# commucation.net
KiCad netlist of a schematic drawn in Altium Designer
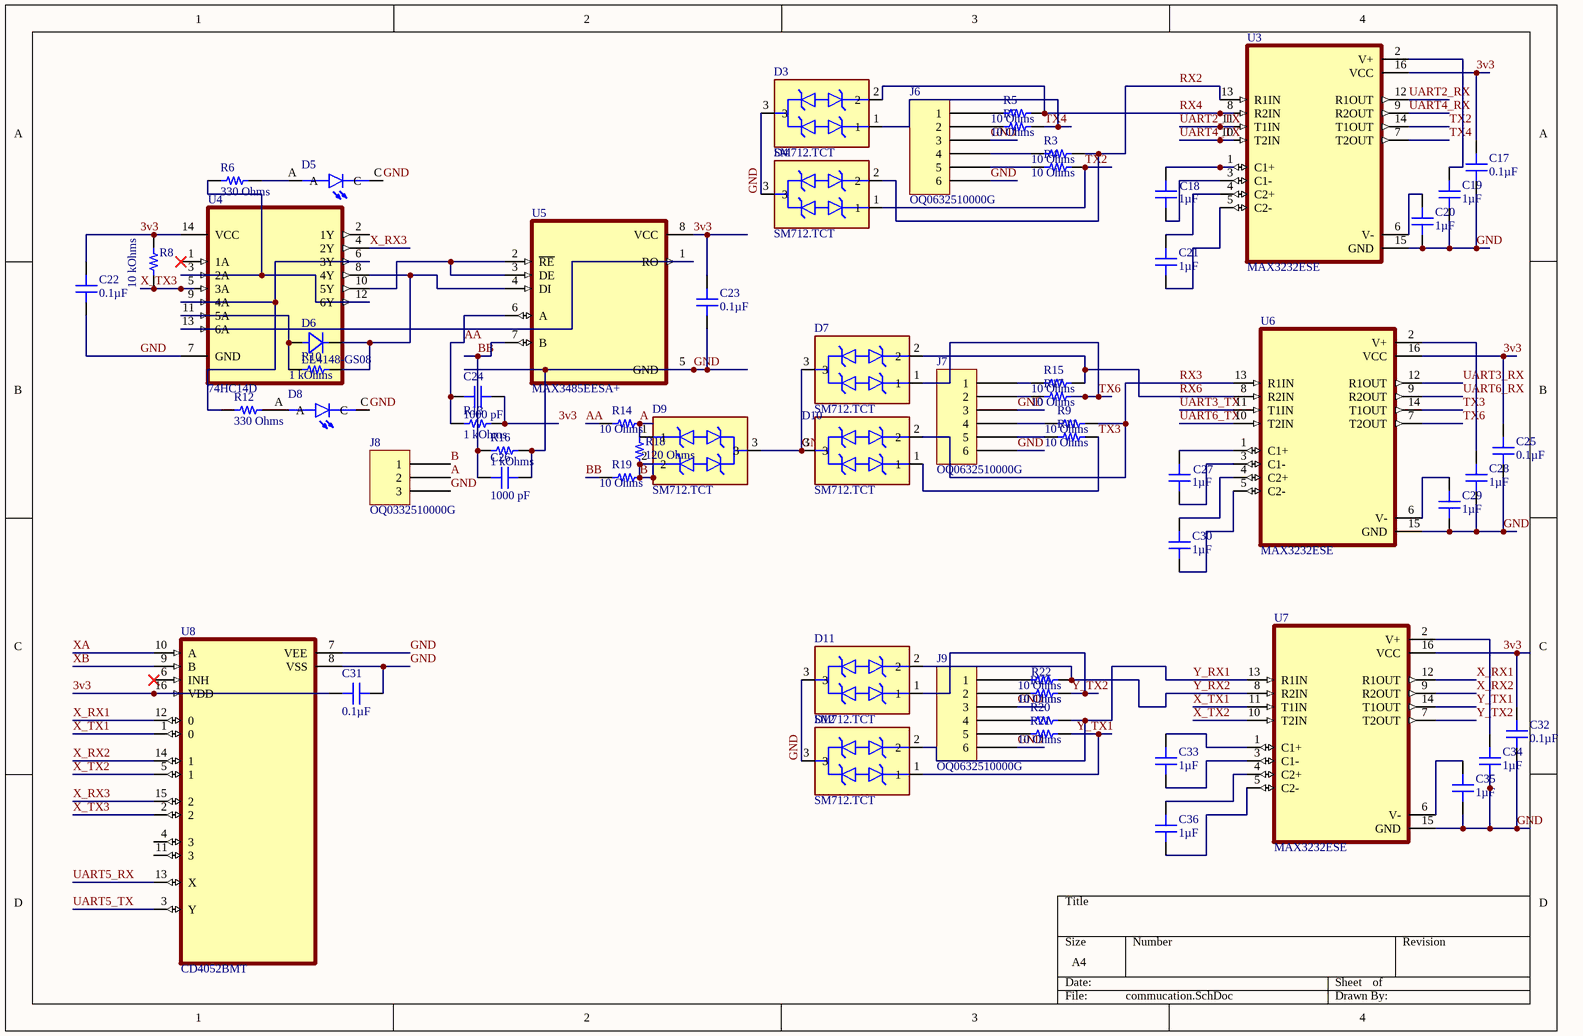
[diagram p0: commucation.SchDoc]

(export (version "E")
  (design (tool "Eeschema 10.0.6"))
  (components
    (comp (ref "C17")
      (value "1µF")
      (footprint "CAP 0805_2012")
      (description "CAP CER 1UF 10V X7R 0805")
      (fields
        (field (name "PART NUMBER") "0805ZC105KAT4A")
        (field (name "CAPACITANCE") "0.1µF")
        (field (name "MANUFACTURER") "AVX Corporation")
      )
      (libsource (lib "Celestial Altium Library - altium_library") (part "Capacitor"))
    )
    (comp (ref "C18")
      (value "1µF")
      (footprint "CAP 0805_2012")
      (description "CAP CER 1UF 10V X7R 0805")
      (fields
        (field (name "PART NUMBER") "0805ZC105KAT4A")
        (field (name "CAPACITANCE") "1µF")
        (field (name "MANUFACTURER") "AVX Corporation")
      )
      (libsource (lib "Celestial Altium Library - altium_library") (part "Capacitor"))
    )
    (comp (ref "C19")
      (value "1µF")
      (footprint "CAP 0805_2012")
      (description "CAP CER 1UF 10V X7R 0805")
      (fields
        (field (name "PART NUMBER") "0805ZC105KAT4A")
        (field (name "CAPACITANCE") "1µF")
        (field (name "MANUFACTURER") "AVX Corporation")
      )
      (libsource (lib "Celestial Altium Library - altium_library") (part "Capacitor"))
    )
    (comp (ref "C20")
      (value "1µF")
      (footprint "CAP 0805_2012")
      (description "CAP CER 1UF 10V X7R 0805")
      (fields
        (field (name "PART NUMBER") "0805ZC105KAT4A")
        (field (name "CAPACITANCE") "1µF")
        (field (name "MANUFACTURER") "AVX Corporation")
      )
      (libsource (lib "Celestial Altium Library - altium_library") (part "Capacitor"))
    )
    (comp (ref "C21")
      (value "1µF")
      (footprint "CAP 0805_2012")
      (description "CAP CER 1UF 10V X7R 0805")
      (fields
        (field (name "PART NUMBER") "0805ZC105KAT4A")
        (field (name "CAPACITANCE") "1µF")
        (field (name "MANUFACTURER") "AVX Corporation")
      )
      (libsource (lib "Celestial Altium Library - altium_library") (part "Capacitor"))
    )
    (comp (ref "C22")
      (value "1µF")
      (footprint "CAP 0805_2012")
      (description "CAP CER 1UF 10V X7R 0805")
      (fields
        (field (name "PART NUMBER") "0805ZC105KAT4A")
        (field (name "CAPACITANCE") "0.1µF")
        (field (name "MANUFACTURER") "AVX Corporation")
      )
      (libsource (lib "Celestial Altium Library - altium_library") (part "Capacitor"))
    )
    (comp (ref "C23")
      (value "1µF")
      (footprint "CAP 0805_2012")
      (description "CAP CER 1UF 10V X7R 0805")
      (fields
        (field (name "PART NUMBER") "0805ZC105KAT4A")
        (field (name "CAPACITANCE") "0.1µF")
        (field (name "MANUFACTURER") "AVX Corporation")
      )
      (libsource (lib "Celestial Altium Library - altium_library") (part "Capacitor"))
    )
    (comp (ref "C24")
      (value "1000 pF")
      (footprint "CAP 0805_2012")
      (description "CAP CER 0805 1NF 25V ULTRA STABL")
      (fields
        (field (name "PART NUMBER") "C0805C102F3HACAUTO")
        (field (name "CAPACITANCE") "1000 pF")
        (field (name "MANUFACTURER") "KEMET")
      )
      (libsource (lib "Celestial Altium Library - altium_library") (part "Capacitor"))
    )
    (comp (ref "C25")
      (value "1µF")
      (footprint "CAP 0805_2012")
      (description "CAP CER 1UF 10V X7R 0805")
      (fields
        (field (name "PART NUMBER") "0805ZC105KAT4A")
        (field (name "CAPACITANCE") "0.1µF")
        (field (name "MANUFACTURER") "AVX Corporation")
      )
      (libsource (lib "Celestial Altium Library - altium_library") (part "Capacitor"))
    )
    (comp (ref "C26")
      (value "1000 pF")
      (footprint "CAP 0805_2012")
      (description "CAP CER 0805 1NF 25V ULTRA STABL")
      (fields
        (field (name "PART NUMBER") "C0805C102F3HACAUTO")
        (field (name "CAPACITANCE") "1000 pF")
        (field (name "MANUFACTURER") "KEMET")
      )
      (libsource (lib "Celestial Altium Library - altium_library") (part "Capacitor"))
    )
    (comp (ref "C27")
      (value "1µF")
      (footprint "CAP 0805_2012")
      (description "CAP CER 1UF 10V X7R 0805")
      (fields
        (field (name "PART NUMBER") "0805ZC105KAT4A")
        (field (name "CAPACITANCE") "1µF")
        (field (name "MANUFACTURER") "AVX Corporation")
      )
      (libsource (lib "Celestial Altium Library - altium_library") (part "Capacitor"))
    )
    (comp (ref "C28")
      (value "1µF")
      (footprint "CAP 0805_2012")
      (description "CAP CER 1UF 10V X7R 0805")
      (fields
        (field (name "PART NUMBER") "0805ZC105KAT4A")
        (field (name "CAPACITANCE") "1µF")
        (field (name "MANUFACTURER") "AVX Corporation")
      )
      (libsource (lib "Celestial Altium Library - altium_library") (part "Capacitor"))
    )
    (comp (ref "C29")
      (value "1µF")
      (footprint "CAP 0805_2012")
      (description "CAP CER 1UF 10V X7R 0805")
      (fields
        (field (name "PART NUMBER") "0805ZC105KAT4A")
        (field (name "CAPACITANCE") "1µF")
        (field (name "MANUFACTURER") "AVX Corporation")
      )
      (libsource (lib "Celestial Altium Library - altium_library") (part "Capacitor"))
    )
    (comp (ref "C30")
      (value "1µF")
      (footprint "CAP 0805_2012")
      (description "CAP CER 1UF 10V X7R 0805")
      (fields
        (field (name "PART NUMBER") "0805ZC105KAT4A")
        (field (name "CAPACITANCE") "1µF")
        (field (name "MANUFACTURER") "AVX Corporation")
      )
      (libsource (lib "Celestial Altium Library - altium_library") (part "Capacitor"))
    )
    (comp (ref "C31")
      (value "1µF")
      (footprint "CAP 0805_2012")
      (description "CAP CER 1UF 10V X7R 0805")
      (fields
        (field (name "PART NUMBER") "0805ZC105KAT4A")
        (field (name "CAPACITANCE") "0.1µF")
        (field (name "MANUFACTURER") "AVX Corporation")
      )
      (libsource (lib "Celestial Altium Library - altium_library") (part "Capacitor"))
    )
    (comp (ref "C32")
      (value "1µF")
      (footprint "CAP 0805_2012")
      (description "CAP CER 1UF 10V X7R 0805")
      (fields
        (field (name "PART NUMBER") "0805ZC105KAT4A")
        (field (name "CAPACITANCE") "0.1µF")
        (field (name "MANUFACTURER") "AVX Corporation")
      )
      (libsource (lib "Celestial Altium Library - altium_library") (part "Capacitor"))
    )
    (comp (ref "C33")
      (value "1µF")
      (footprint "CAP 0805_2012")
      (description "CAP CER 1UF 10V X7R 0805")
      (fields
        (field (name "PART NUMBER") "0805ZC105KAT4A")
        (field (name "CAPACITANCE") "1µF")
        (field (name "MANUFACTURER") "AVX Corporation")
      )
      (libsource (lib "Celestial Altium Library - altium_library") (part "Capacitor"))
    )
    (comp (ref "C34")
      (value "1µF")
      (footprint "CAP 0805_2012")
      (description "CAP CER 1UF 10V X7R 0805")
      (fields
        (field (name "PART NUMBER") "0805ZC105KAT4A")
        (field (name "CAPACITANCE") "1µF")
        (field (name "MANUFACTURER") "AVX Corporation")
      )
      (libsource (lib "Celestial Altium Library - altium_library") (part "Capacitor"))
    )
    (comp (ref "C35")
      (value "1µF")
      (footprint "CAP 0805_2012")
      (description "CAP CER 1UF 10V X7R 0805")
      (fields
        (field (name "PART NUMBER") "0805ZC105KAT4A")
        (field (name "CAPACITANCE") "1µF")
        (field (name "MANUFACTURER") "AVX Corporation")
      )
      (libsource (lib "Celestial Altium Library - altium_library") (part "Capacitor"))
    )
    (comp (ref "C36")
      (value "1µF")
      (footprint "CAP 0805_2012")
      (description "CAP CER 1UF 10V X7R 0805")
      (fields
        (field (name "PART NUMBER") "0805ZC105KAT4A")
        (field (name "CAPACITANCE") "1µF")
        (field (name "MANUFACTURER") "AVX Corporation")
      )
      (libsource (lib "Celestial Altium Library - altium_library") (part "Capacitor"))
    )
    (comp (ref "D3")
      (value "SM712.TCT")
      (footprint "SM712.TCT")
      (description "SM Series 12 V 400 W Asymmetrical TVS Diode for Extended Common-Mode - SOT-23")
      (fields (field (name "MF") "Semtech Corporation"))
      (libsource (lib "SM712.TCT") (part "SM712.TCT"))
    )
    (comp (ref "D4")
      (value "SM712.TCT")
      (footprint "SM712.TCT")
      (description "SM Series 12 V 400 W Asymmetrical TVS Diode for Extended Common-Mode - SOT-23")
      (fields (field (name "MF") "Semtech Corporation"))
      (libsource (lib "SM712.TCT") (part "SM712.TCT"))
    )
    (comp (ref "D5")
      (value "597-3305-607F")
      (footprint "LEDC2012X70N")
      (description "LED Uni-Color Green 4-Pin Chip 0805 T/R")
      (libsource (lib "597-3305-607F") (part "597-3305-607F"))
    )
    (comp (ref "D6")
      (value "LL4148-GS08")
      (footprint "MELF_SOD-80")
      (description "Diode Standard 75 V 300mA (DC) Surface Mount SOD-80 MiniMELF")
      (fields (field (name "MF") "Vishay General Semiconductor - Diodes Division"))
      (libsource (lib "LL4148-GS08") (part "LL4148-GS08"))
    )
    (comp (ref "D7")
      (value "SM712.TCT")
      (footprint "SM712.TCT")
      (description "SM Series 12 V 400 W Asymmetrical TVS Diode for Extended Common-Mode - SOT-23")
      (fields (field (name "MF") "Semtech Corporation"))
      (libsource (lib "SM712.TCT") (part "SM712.TCT"))
    )
    (comp (ref "D8")
      (value "597-3305-607F")
      (footprint "LEDC2012X70N")
      (description "LED Uni-Color Green 4-Pin Chip 0805 T/R")
      (libsource (lib "597-3305-607F") (part "597-3305-607F"))
    )
    (comp (ref "D9")
      (value "SM712.TCT")
      (footprint "SM712.TCT")
      (description "SM Series 12 V 400 W Asymmetrical TVS Diode for Extended Common-Mode - SOT-23")
      (fields (field (name "MF") "Semtech Corporation"))
      (libsource (lib "SM712.TCT") (part "SM712.TCT"))
    )
    (comp (ref "D10")
      (value "SM712.TCT")
      (footprint "SM712.TCT")
      (description "SM Series 12 V 400 W Asymmetrical TVS Diode for Extended Common-Mode - SOT-23")
      (fields (field (name "MF") "Semtech Corporation"))
      (libsource (lib "SM712.TCT") (part "SM712.TCT"))
    )
    (comp (ref "D11")
      (value "SM712.TCT")
      (footprint "SM712.TCT")
      (description "SM Series 12 V 400 W Asymmetrical TVS Diode for Extended Common-Mode - SOT-23")
      (fields (field (name "MF") "Semtech Corporation"))
      (libsource (lib "SM712.TCT") (part "SM712.TCT"))
    )
    (comp (ref "D12")
      (value "SM712.TCT")
      (footprint "SM712.TCT")
      (description "SM Series 12 V 400 W Asymmetrical TVS Diode for Extended Common-Mode - SOT-23")
      (fields (field (name "MF") "Semtech Corporation"))
      (libsource (lib "SM712.TCT") (part "SM712.TCT"))
    )
    (comp (ref "J6")
      (value "OQ0632510000G")
      (footprint "FCI 06-381-6PIN")
      (description "TERM BLOCK HDR 6POS 90DEG 3.81MM")
      (fields (field (name "MANUFACTURER") "Amphenol Anytek"))
      (libsource (lib "Celestial Altium Library - altium_library") (part "6 Pin"))
    )
    (comp (ref "J7")
      (value "OQ0632510000G")
      (footprint "FCI 06-381-6PIN")
      (description "TERM BLOCK HDR 6POS 90DEG 3.81MM")
      (fields (field (name "MANUFACTURER") "Amphenol Anytek"))
      (libsource (lib "Celestial Altium Library - altium_library") (part "6 Pin"))
    )
    (comp (ref "J8")
      (value "OQ0332510000G")
      (footprint "FCI 06-381-3PIN")
      (description "TERM BLOCK HDR 3POS 90DEG 3.81MM")
      (fields (field (name "MANUFACTURER") "Amphenol Anytek"))
      (libsource (lib "Celestial Altium Library - altium_library") (part "3 Pin"))
    )
    (comp (ref "J9")
      (value "OQ0632510000G")
      (footprint "FCI 06-381-6PIN")
      (description "TERM BLOCK HDR 6POS 90DEG 3.81MM")
      (fields (field (name "MANUFACTURER") "Amphenol Anytek"))
      (libsource (lib "Celestial Altium Library - altium_library") (part "6 Pin"))
    )
    (comp (ref "R3")
      (value "10 Ohms")
      (footprint "RES 0805_2012")
      (description "RES 10 OHM 0.1% 1/10W 0805")
      (fields
        (field (name "PART NUMBER") "RNCS0805BKE10R0")
        (field (name "MANUFACTURER") "Stackpole Electronics Inc")
      )
      (libsource (lib "Celestial Altium Library - altium_library") (part "Resistor"))
    )
    (comp (ref "R4")
      (value "10 Ohms")
      (footprint "RES 0805_2012")
      (description "RES 10 OHM 0.1% 1/10W 0805")
      (fields
        (field (name "PART NUMBER") "RNCS0805BKE10R0")
        (field (name "MANUFACTURER") "Stackpole Electronics Inc")
      )
      (libsource (lib "Celestial Altium Library - altium_library") (part "Resistor"))
    )
    (comp (ref "R5")
      (value "10 Ohms")
      (footprint "RES 0805_2012")
      (description "RES 10 OHM 0.1% 1/10W 0805")
      (fields
        (field (name "PART NUMBER") "RNCS0805BKE10R0")
        (field (name "MANUFACTURER") "Stackpole Electronics Inc")
      )
      (libsource (lib "Celestial Altium Library - altium_library") (part "Resistor"))
    )
    (comp (ref "R6")
      (value "330 Ohms")
      (footprint "RES 0805_2012")
      (description "RES SMD 330 OHM 1% 1/2W 0805")
      (fields (field (name "PART NUMBER") "CRCW0805330RFKEAHP") (field (name "MANUFACTURER") "Vishay Dale"))
      (libsource (lib "Celestial Altium Library - altium_library") (part "Resistor"))
    )
    (comp (ref "R7")
      (value "10 Ohms")
      (footprint "RES 0805_2012")
      (description "RES 10 OHM 0.1% 1/10W 0805")
      (fields
        (field (name "PART NUMBER") "RNCS0805BKE10R0")
        (field (name "MANUFACTURER") "Stackpole Electronics Inc")
      )
      (libsource (lib "Celestial Altium Library - altium_library") (part "Resistor"))
    )
    (comp (ref "R8")
      (value "10 kOhms")
      (footprint "RES 0805_2012")
      (description "RES SMD 10K OHM 0.1% 1/10W 0805")
      (fields
        (field (name "PART NUMBER") "CPF0805B10KE")
        (field (name "MANUFACTURER") "TE Connectivity Passive Product")
      )
      (libsource (lib "Celestial Altium Library - altium_library") (part "Resistor"))
    )
    (comp (ref "R9")
      (value "10 Ohms")
      (footprint "RES 0805_2012")
      (description "RES 10 OHM 0.1% 1/10W 0805")
      (fields
        (field (name "PART NUMBER") "RNCS0805BKE10R0")
        (field (name "MANUFACTURER") "Stackpole Electronics Inc")
      )
      (libsource (lib "Celestial Altium Library - altium_library") (part "Resistor"))
    )
    (comp (ref "R10")
      (value "1 kOhms")
      (footprint "RES 0805_2012")
      (description "RES SMD 1K OHM 0.1% 1/10W 0805")
      (fields
        (field (name "PART NUMBER") "CPF0805B1K0E")
        (field (name "MANUFACTURER") "TE Connectivity Passive Product")
      )
      (libsource (lib "Celestial Altium Library - altium_library") (part "Resistor"))
    )
    (comp (ref "R11")
      (value "10 Ohms")
      (footprint "RES 0805_2012")
      (description "RES 10 OHM 0.1% 1/10W 0805")
      (fields
        (field (name "PART NUMBER") "RNCS0805BKE10R0")
        (field (name "MANUFACTURER") "Stackpole Electronics Inc")
      )
      (libsource (lib "Celestial Altium Library - altium_library") (part "Resistor"))
    )
    (comp (ref "R12")
      (value "330 Ohms")
      (footprint "RES 0805_2012")
      (description "RES SMD 330 OHM 1% 1/2W 0805")
      (fields (field (name "PART NUMBER") "CRCW0805330RFKEAHP") (field (name "MANUFACTURER") "Vishay Dale"))
      (libsource (lib "Celestial Altium Library - altium_library") (part "Resistor"))
    )
    (comp (ref "R13")
      (value "1 kOhms")
      (footprint "RES 0805_2012")
      (description "RES SMD 1K OHM 0.1% 1/10W 0805")
      (fields
        (field (name "PART NUMBER") "CPF0805B1K0E")
        (field (name "MANUFACTURER") "TE Connectivity Passive Product")
      )
      (libsource (lib "Celestial Altium Library - altium_library") (part "Resistor"))
    )
    (comp (ref "R14")
      (value "10 Ohms")
      (footprint "RES 0805_2012")
      (description "RES 10 OHM 0.1% 1/10W 0805")
      (fields
        (field (name "PART NUMBER") "RNCS0805BKE10R0")
        (field (name "MANUFACTURER") "Stackpole Electronics Inc")
      )
      (libsource (lib "Celestial Altium Library - altium_library") (part "Resistor"))
    )
    (comp (ref "R15")
      (value "10 Ohms")
      (footprint "RES 0805_2012")
      (description "RES 10 OHM 0.1% 1/10W 0805")
      (fields
        (field (name "PART NUMBER") "RNCS0805BKE10R0")
        (field (name "MANUFACTURER") "Stackpole Electronics Inc")
      )
      (libsource (lib "Celestial Altium Library - altium_library") (part "Resistor"))
    )
    (comp (ref "R16")
      (value "1 kOhms")
      (footprint "RES 0805_2012")
      (description "RES SMD 1K OHM 0.1% 1/10W 0805")
      (fields
        (field (name "PART NUMBER") "CPF0805B1K0E")
        (field (name "MANUFACTURER") "TE Connectivity Passive Product")
      )
      (libsource (lib "Celestial Altium Library - altium_library") (part "Resistor"))
    )
    (comp (ref "R17")
      (value "10 Ohms")
      (footprint "RES 0805_2012")
      (description "RES 10 OHM 0.1% 1/10W 0805")
      (fields
        (field (name "PART NUMBER") "RNCS0805BKE10R0")
        (field (name "MANUFACTURER") "Stackpole Electronics Inc")
      )
      (libsource (lib "Celestial Altium Library - altium_library") (part "Resistor"))
    )
    (comp (ref "R18")
      (value "120 Ohms")
      (footprint "RES 0805_2012")
      (description "RES 120 OHM 1% 1/8W 0805")
      (fields
        (field (name "PART NUMBER") "RMCF0805FT120R")
        (field (name "MANUFACTURER") "Stackpole Electronics Inc")
      )
      (libsource (lib "Celestial Altium Library - altium_library") (part "Resistor"))
    )
    (comp (ref "R19")
      (value "10 Ohms")
      (footprint "RES 0805_2012")
      (description "RES 10 OHM 0.1% 1/10W 0805")
      (fields
        (field (name "PART NUMBER") "RNCS0805BKE10R0")
        (field (name "MANUFACTURER") "Stackpole Electronics Inc")
      )
      (libsource (lib "Celestial Altium Library - altium_library") (part "Resistor"))
    )
    (comp (ref "R20")
      (value "10 Ohms")
      (footprint "RES 0805_2012")
      (description "RES 10 OHM 0.1% 1/10W 0805")
      (fields
        (field (name "PART NUMBER") "RNCS0805BKE10R0")
        (field (name "MANUFACTURER") "Stackpole Electronics Inc")
      )
      (libsource (lib "Celestial Altium Library - altium_library") (part "Resistor"))
    )
    (comp (ref "R21")
      (value "10 Ohms")
      (footprint "RES 0805_2012")
      (description "RES 10 OHM 0.1% 1/10W 0805")
      (fields
        (field (name "PART NUMBER") "RNCS0805BKE10R0")
        (field (name "MANUFACTURER") "Stackpole Electronics Inc")
      )
      (libsource (lib "Celestial Altium Library - altium_library") (part "Resistor"))
    )
    (comp (ref "R22")
      (value "10 Ohms")
      (footprint "RES 0805_2012")
      (description "RES 10 OHM 0.1% 1/10W 0805")
      (fields
        (field (name "PART NUMBER") "RNCS0805BKE10R0")
        (field (name "MANUFACTURER") "Stackpole Electronics Inc")
      )
      (libsource (lib "Celestial Altium Library - altium_library") (part "Resistor"))
    )
    (comp (ref "R23")
      (value "10 Ohms")
      (footprint "RES 0805_2012")
      (description "RES 10 OHM 0.1% 1/10W 0805")
      (fields
        (field (name "PART NUMBER") "RNCS0805BKE10R0")
        (field (name "MANUFACTURER") "Stackpole Electronics Inc")
      )
      (libsource (lib "Celestial Altium Library - altium_library") (part "Resistor"))
    )
    (comp (ref "U3")
      (value "MAX3232ESE")
      (footprint "SOIC127P600X175-16N")
      (description "Dual Transmitter/Receiver RS-232 16-Pin SOIC N T/R")
      (fields (field (name "MF") "Analog Devices") (field (name "MP") "MAX3232ESE+T"))
      (libsource (lib "MAX3232ESE") (part "MAX3232ESE"))
    )
    (comp (ref "U4")
      (value "74HC14D")
      (footprint "SOIC127P600X175-14N")
      (description "Inverter IC 6 Channel Schmitt Trigger 14-SOIC")
      (fields (field (name "MF") "Toshiba"))
      (libsource (lib "74HC14D (1)") (part "74HC14D"))
    )
    (comp (ref "U5")
      (value "MAX3485EESA+")
      (footprint "SOIC127P600X175-8N")
      (description "3.3V Powered, Â±15kV ESD-Protected, 12Mbps, Slew-Rate-Limited True RS-485/RS-422 Transceivers")
      (fields (field (name "MF") "Analog Devices"))
      (libsource (lib "MAX3485EESA_") (part "MAX3485EESA+"))
    )
    (comp (ref "U6")
      (value "MAX3232ESE")
      (footprint "SOIC127P600X175-16N")
      (description "Dual Transmitter/Receiver RS-232 16-Pin SOIC N T/R")
      (fields (field (name "MF") "Analog Devices") (field (name "MP") "MAX3232ESE+T"))
      (libsource (lib "MAX3232ESE") (part "MAX3232ESE"))
    )
    (comp (ref "U7")
      (value "MAX3232ESE")
      (footprint "SOIC127P600X175-16N")
      (description "Dual Transmitter/Receiver RS-232 16-Pin SOIC N T/R")
      (fields (field (name "MF") "Analog Devices") (field (name "MP") "MAX3232ESE+T"))
      (libsource (lib "MAX3232ESE") (part "MAX3232ESE"))
    )
    (comp (ref "U8")
      (value "CD4052BMT")
      (footprint "SOIC127P600X175-16N")
      (description "20-V, 4:1, 2-channel general-purpose multiplexer")
      (fields (field (name "MF") "Texas Instruments"))
      (libsource (lib "CD4052BMT") (part "CD4052BMT"))
    )
  )
  (nets
    (net (code "1") (name "/3v3") (class "Default")
      (node (ref "C17") (pin "2") (pinfunction "2_2") (pintype "passive"))
      (node (ref "C22") (pin "2") (pinfunction "2_2") (pintype "passive"))
      (node (ref "C23") (pin "2") (pinfunction "2_2") (pintype "passive"))
      (node (ref "C24") (pin "2") (pinfunction "2_2") (pintype "passive"))
      (node (ref "C25") (pin "2") (pinfunction "2_2") (pintype "passive"))
      (node (ref "C31") (pin "1") (pinfunction "1_1") (pintype "passive"))
      (node (ref "C32") (pin "2") (pinfunction "2_2") (pintype "passive"))
      (node (ref "R13") (pin "2") (pinfunction "2_2") (pintype "passive"))
      (node (ref "R8") (pin "2") (pinfunction "2_2") (pintype "passive"))
      (node (ref "U3") (pin "16") (pinfunction "VCC_16") (pintype "power_in"))
      (node (ref "U4") (pin "14") (pinfunction "VCC_14") (pintype "power_in"))
      (node (ref "U5") (pin "8") (pinfunction "VCC_8") (pintype "power_in"))
      (node (ref "U6") (pin "16") (pinfunction "VCC_16") (pintype "power_in"))
      (node (ref "U7") (pin "16") (pinfunction "VCC_16") (pintype "power_in"))
      (node (ref "U8") (pin "16") (pinfunction "VDD_16") (pintype "input"))
    )
    (net (code "2") (name "/A") (class "Default")
      (node (ref "D9") (pin "1") (pinfunction "1_1") (pintype "bidirectional"))
      (node (ref "J8") (pin "2") (pinfunction "2_2") (pintype "passive"))
      (node (ref "R14") (pin "2") (pinfunction "2_2") (pintype "passive"))
      (node (ref "R18") (pin "2") (pinfunction "2_2") (pintype "passive"))
    )
    (net (code "3") (name "/AA") (class "Default")
      (node (ref "C24") (pin "1") (pinfunction "1_1") (pintype "passive"))
      (node (ref "R13") (pin "1") (pinfunction "1_1") (pintype "passive"))
      (node (ref "R14") (pin "1") (pinfunction "1_1") (pintype "passive"))
      (node (ref "U5") (pin "6") (pinfunction "A_6") (pintype "bidirectional"))
    )
    (net (code "4") (name "/B") (class "Default")
      (node (ref "D9") (pin "2") (pinfunction "2_2") (pintype "bidirectional"))
      (node (ref "J8") (pin "1") (pinfunction "1_1") (pintype "passive"))
      (node (ref "R18") (pin "1") (pinfunction "1_1") (pintype "passive"))
      (node (ref "R19") (pin "2") (pinfunction "2_2") (pintype "passive"))
    )
    (net (code "5") (name "/BB") (class "Default")
      (node (ref "C26") (pin "1") (pinfunction "1_1") (pintype "passive"))
      (node (ref "R16") (pin "1") (pinfunction "1_1") (pintype "passive"))
      (node (ref "R19") (pin "1") (pinfunction "1_1") (pintype "passive"))
      (node (ref "U5") (pin "7") (pinfunction "B_7") (pintype "bidirectional"))
    )
    (net (code "6") (name "/GND") (class "Default")
      (node (ref "C17") (pin "1") (pinfunction "1_1") (pintype "passive"))
      (node (ref "C19") (pin "1") (pinfunction "1_1") (pintype "passive"))
      (node (ref "C20") (pin "1") (pinfunction "1_1") (pintype "passive"))
      (node (ref "C22") (pin "1") (pinfunction "1_1") (pintype "passive"))
      (node (ref "C23") (pin "1") (pinfunction "1_1") (pintype "passive"))
      (node (ref "C25") (pin "1") (pinfunction "1_1") (pintype "passive"))
      (node (ref "C26") (pin "2") (pinfunction "2_2") (pintype "passive"))
      (node (ref "C28") (pin "1") (pinfunction "1_1") (pintype "passive"))
      (node (ref "C29") (pin "1") (pinfunction "1_1") (pintype "passive"))
      (node (ref "C31") (pin "2") (pinfunction "2_2") (pintype "passive"))
      (node (ref "C32") (pin "1") (pinfunction "1_1") (pintype "passive"))
      (node (ref "C34") (pin "1") (pinfunction "1_1") (pintype "passive"))
      (node (ref "C35") (pin "1") (pinfunction "1_1") (pintype "passive"))
      (node (ref "D10") (pin "3") (pinfunction "3_3") (pintype "bidirectional"))
      (node (ref "D11") (pin "3") (pinfunction "3_3") (pintype "bidirectional"))
      (node (ref "D12") (pin "3") (pinfunction "3_3") (pintype "bidirectional"))
      (node (ref "D3") (pin "3") (pinfunction "3_3") (pintype "bidirectional"))
      (node (ref "D4") (pin "3") (pinfunction "3_3") (pintype "bidirectional"))
      (node (ref "D5") (pin "C") (pinfunction "C_C") (pintype "passive"))
      (node (ref "D7") (pin "3") (pinfunction "3_3") (pintype "bidirectional"))
      (node (ref "D8") (pin "C") (pinfunction "C_C") (pintype "passive"))
      (node (ref "D9") (pin "3") (pinfunction "3_3") (pintype "bidirectional"))
      (node (ref "J6") (pin "3") (pinfunction "3_3") (pintype "passive"))
      (node (ref "J6") (pin "6") (pinfunction "6_6") (pintype "passive"))
      (node (ref "J7") (pin "3") (pinfunction "3_3") (pintype "passive"))
      (node (ref "J7") (pin "6") (pinfunction "6_6") (pintype "passive"))
      (node (ref "J8") (pin "3") (pinfunction "3_3") (pintype "passive"))
      (node (ref "J9") (pin "3") (pinfunction "3_3") (pintype "passive"))
      (node (ref "J9") (pin "6") (pinfunction "6_6") (pintype "passive"))
      (node (ref "R16") (pin "2") (pinfunction "2_2") (pintype "passive"))
      (node (ref "U3") (pin "15") (pinfunction "GND_15") (pintype "power_in"))
      (node (ref "U4") (pin "7") (pinfunction "GND_7") (pintype "passive"))
      (node (ref "U5") (pin "5") (pinfunction "GND_5") (pintype "power_in"))
      (node (ref "U6") (pin "15") (pinfunction "GND_15") (pintype "power_in"))
      (node (ref "U7") (pin "15") (pinfunction "GND_15") (pintype "power_in"))
      (node (ref "U8") (pin "7") (pinfunction "VEE_7") (pintype "power_in"))
      (node (ref "U8") (pin "8") (pinfunction "VSS_8") (pintype "power_in"))
    )
    (net (code "7") (name "/RX2") (class "Default")
      (node (ref "D4") (pin "2") (pinfunction "2_2") (pintype "bidirectional"))
      (node (ref "R3") (pin "2") (pinfunction "2_2") (pintype "passive"))
      (node (ref "U3") (pin "13") (pinfunction "R1IN_13") (pintype "input"))
    )
    (net (code "8") (name "/RX3") (class "Default")
      (node (ref "D10") (pin "2") (pinfunction "2_2") (pintype "bidirectional"))
      (node (ref "R9") (pin "2") (pinfunction "2_2") (pintype "passive"))
      (node (ref "U6") (pin "13") (pinfunction "R1IN_13") (pintype "input"))
    )
    (net (code "9") (name "/RX4") (class "Default")
      (node (ref "D3") (pin "2") (pinfunction "2_2") (pintype "bidirectional"))
      (node (ref "R5") (pin "2") (pinfunction "2_2") (pintype "passive"))
      (node (ref "U3") (pin "8") (pinfunction "R2IN_8") (pintype "input"))
    )
    (net (code "10") (name "/RX6") (class "Default")
      (node (ref "D7") (pin "2") (pinfunction "2_2") (pintype "bidirectional"))
      (node (ref "R15") (pin "2") (pinfunction "2_2") (pintype "passive"))
      (node (ref "U6") (pin "8") (pinfunction "R2IN_8") (pintype "input"))
    )
    (net (code "11") (name "/TX2") (class "Default")
      (node (ref "D4") (pin "1") (pinfunction "1_1") (pintype "bidirectional"))
      (node (ref "R4") (pin "2") (pinfunction "2_2") (pintype "passive"))
      (node (ref "U3") (pin "14") (pinfunction "T1OUT_14") (pintype "output"))
    )
    (net (code "12") (name "/TX3") (class "Default")
      (node (ref "D10") (pin "1") (pinfunction "1_1") (pintype "bidirectional"))
      (node (ref "R11") (pin "2") (pinfunction "2_2") (pintype "passive"))
      (node (ref "U6") (pin "14") (pinfunction "T1OUT_14") (pintype "output"))
    )
    (net (code "13") (name "/TX4") (class "Default")
      (node (ref "D3") (pin "1") (pinfunction "1_1") (pintype "bidirectional"))
      (node (ref "R7") (pin "2") (pinfunction "2_2") (pintype "passive"))
      (node (ref "U3") (pin "7") (pinfunction "T2OUT_7") (pintype "output"))
    )
    (net (code "14") (name "/TX6") (class "Default")
      (node (ref "D7") (pin "1") (pinfunction "1_1") (pintype "bidirectional"))
      (node (ref "R17") (pin "2") (pinfunction "2_2") (pintype "passive"))
      (node (ref "U6") (pin "7") (pinfunction "T2OUT_7") (pintype "output"))
    )
    (net (code "15") (name "/UART2_RX") (class "Default")
      (node (ref "U3") (pin "12") (pinfunction "R1OUT_12") (pintype "output"))
    )
    (net (code "16") (name "/UART2_TX") (class "Default")
      (node (ref "U3") (pin "11") (pinfunction "T1IN_11") (pintype "input"))
    )
    (net (code "17") (name "/UART3_RX") (class "Default")
      (node (ref "U6") (pin "12") (pinfunction "R1OUT_12") (pintype "output"))
    )
    (net (code "18") (name "/UART3_TX") (class "Default")
      (node (ref "U6") (pin "11") (pinfunction "T1IN_11") (pintype "input"))
    )
    (net (code "19") (name "/UART4_RX") (class "Default")
      (node (ref "U3") (pin "9") (pinfunction "R2OUT_9") (pintype "output"))
    )
    (net (code "20") (name "/UART4_TX") (class "Default")
      (node (ref "U3") (pin "10") (pinfunction "T2IN_10") (pintype "input"))
    )
    (net (code "21") (name "/UART5_RX") (class "Default")
      (node (ref "U8") (pin "13") (pinfunction "X_13") (pintype "bidirectional"))
    )
    (net (code "22") (name "/UART5_TX") (class "Default")
      (node (ref "U8") (pin "3") (pinfunction "Y_3") (pintype "bidirectional"))
    )
    (net (code "23") (name "/UART6_RX") (class "Default")
      (node (ref "U6") (pin "9") (pinfunction "R2OUT_9") (pintype "output"))
    )
    (net (code "24") (name "/UART6_TX") (class "Default")
      (node (ref "U6") (pin "10") (pinfunction "T2IN_10") (pintype "input"))
    )
    (net (code "25") (name "/XA") (class "Default")
      (node (ref "U8") (pin "10") (pinfunction "A_10") (pintype "input"))
    )
    (net (code "26") (name "/XB") (class "Default")
      (node (ref "U8") (pin "9") (pinfunction "B_9") (pintype "input"))
    )
    (net (code "27") (name "/X_RX1") (class "Default")
      (node (ref "U7") (pin "12") (pinfunction "R1OUT_12") (pintype "output"))
      (node (ref "U8") (pin "12") (pinfunction "0_12") (pintype "bidirectional"))
    )
    (net (code "28") (name "/X_RX2") (class "Default")
      (node (ref "U7") (pin "9") (pinfunction "R2OUT_9") (pintype "output"))
      (node (ref "U8") (pin "14") (pinfunction "1_14") (pintype "bidirectional"))
    )
    (net (code "29") (name "/X_RX3") (class "Default")
      (node (ref "U4") (pin "4") (pinfunction "2Y_4") (pintype "output"))
      (node (ref "U8") (pin "15") (pinfunction "2_15") (pintype "bidirectional"))
    )
    (net (code "30") (name "/X_TX1") (class "Default")
      (node (ref "U7") (pin "11") (pinfunction "T1IN_11") (pintype "input"))
      (node (ref "U8") (pin "1") (pinfunction "0_1") (pintype "bidirectional"))
    )
    (net (code "31") (name "/X_TX2") (class "Default")
      (node (ref "U7") (pin "10") (pinfunction "T2IN_10") (pintype "input"))
      (node (ref "U8") (pin "5") (pinfunction "1_5") (pintype "bidirectional"))
    )
    (net (code "32") (name "/X_TX3") (class "Default")
      (node (ref "R8") (pin "1") (pinfunction "1_1") (pintype "passive"))
      (node (ref "U4") (pin "5") (pinfunction "3A_5") (pintype "input"))
      (node (ref "U8") (pin "2") (pinfunction "2_2") (pintype "bidirectional"))
    )
    (net (code "33") (name "/Y_RX1") (class "Default")
      (node (ref "D12") (pin "2") (pinfunction "2_2") (pintype "bidirectional"))
      (node (ref "R20") (pin "2") (pinfunction "2_2") (pintype "passive"))
      (node (ref "U7") (pin "13") (pinfunction "R1IN_13") (pintype "input"))
    )
    (net (code "34") (name "/Y_RX2") (class "Default")
      (node (ref "D11") (pin "2") (pinfunction "2_2") (pintype "bidirectional"))
      (node (ref "R22") (pin "2") (pinfunction "2_2") (pintype "passive"))
      (node (ref "U7") (pin "8") (pinfunction "R2IN_8") (pintype "input"))
    )
    (net (code "35") (name "/Y_TX1") (class "Default")
      (node (ref "D12") (pin "1") (pinfunction "1_1") (pintype "bidirectional"))
      (node (ref "R21") (pin "2") (pinfunction "2_2") (pintype "passive"))
      (node (ref "U7") (pin "14") (pinfunction "T1OUT_14") (pintype "output"))
    )
    (net (code "36") (name "/Y_TX2") (class "Default")
      (node (ref "D11") (pin "1") (pinfunction "1_1") (pintype "bidirectional"))
      (node (ref "R23") (pin "2") (pinfunction "2_2") (pintype "passive"))
      (node (ref "U7") (pin "7") (pinfunction "T2OUT_7") (pintype "output"))
    )
    (net (code "37") (name "Net-(D5-PadA)") (class "Default")
      (node (ref "D5") (pin "A") (pinfunction "A_A") (pintype "passive"))
      (node (ref "R6") (pin "2") (pinfunction "2_2") (pintype "passive"))
    )
    (net (code "38") (name "Net-(D8-PadA)") (class "Default")
      (node (ref "D8") (pin "A") (pinfunction "A_A") (pintype "passive"))
      (node (ref "R12") (pin "2") (pinfunction "2_2") (pintype "passive"))
    )
    (net (code "39") (name "Net-(J6-Pad1)") (class "Default")
      (node (ref "J6") (pin "1") (pinfunction "1_1") (pintype "passive"))
      (node (ref "R5") (pin "1") (pinfunction "1_1") (pintype "passive"))
    )
    (net (code "40") (name "Net-(J6-Pad2)") (class "Default")
      (node (ref "J6") (pin "2") (pinfunction "2_2") (pintype "passive"))
      (node (ref "R7") (pin "1") (pinfunction "1_1") (pintype "passive"))
    )
    (net (code "41") (name "Net-(J6-Pad4)") (class "Default")
      (node (ref "J6") (pin "4") (pinfunction "4_4") (pintype "passive"))
      (node (ref "R3") (pin "1") (pinfunction "1_1") (pintype "passive"))
    )
    (net (code "42") (name "Net-(J6-Pad5)") (class "Default")
      (node (ref "J6") (pin "5") (pinfunction "5_5") (pintype "passive"))
      (node (ref "R4") (pin "1") (pinfunction "1_1") (pintype "passive"))
    )
    (net (code "43") (name "Net-(J7-Pad1)") (class "Default")
      (node (ref "J7") (pin "1") (pinfunction "1_1") (pintype "passive"))
      (node (ref "R15") (pin "1") (pinfunction "1_1") (pintype "passive"))
    )
    (net (code "44") (name "Net-(J7-Pad2)") (class "Default")
      (node (ref "J7") (pin "2") (pinfunction "2_2") (pintype "passive"))
      (node (ref "R17") (pin "1") (pinfunction "1_1") (pintype "passive"))
    )
    (net (code "45") (name "Net-(J7-Pad4)") (class "Default")
      (node (ref "J7") (pin "4") (pinfunction "4_4") (pintype "passive"))
      (node (ref "R9") (pin "1") (pinfunction "1_1") (pintype "passive"))
    )
    (net (code "46") (name "Net-(J7-Pad5)") (class "Default")
      (node (ref "J7") (pin "5") (pinfunction "5_5") (pintype "passive"))
      (node (ref "R11") (pin "1") (pinfunction "1_1") (pintype "passive"))
    )
    (net (code "47") (name "Net-(J9-Pad1)") (class "Default")
      (node (ref "J9") (pin "1") (pinfunction "1_1") (pintype "passive"))
      (node (ref "R22") (pin "1") (pinfunction "1_1") (pintype "passive"))
    )
    (net (code "48") (name "Net-(J9-Pad2)") (class "Default")
      (node (ref "J9") (pin "2") (pinfunction "2_2") (pintype "passive"))
      (node (ref "R23") (pin "1") (pinfunction "1_1") (pintype "passive"))
    )
    (net (code "49") (name "Net-(J9-Pad4)") (class "Default")
      (node (ref "J9") (pin "4") (pinfunction "4_4") (pintype "passive"))
      (node (ref "R20") (pin "1") (pinfunction "1_1") (pintype "passive"))
    )
    (net (code "50") (name "Net-(J9-Pad5)") (class "Default")
      (node (ref "J9") (pin "5") (pinfunction "5_5") (pintype "passive"))
      (node (ref "R21") (pin "1") (pinfunction "1_1") (pintype "passive"))
    )
    (net (code "51") (name "Net-(U3-C1+)") (class "Default")
      (node (ref "C18") (pin "2") (pinfunction "2_2") (pintype "passive"))
      (node (ref "U3") (pin "1") (pinfunction "C1+_1") (pintype "bidirectional"))
    )
    (net (code "52") (name "Net-(U3-C1-)") (class "Default")
      (node (ref "C18") (pin "1") (pinfunction "1_1") (pintype "passive"))
      (node (ref "U3") (pin "3") (pinfunction "C1-_3") (pintype "bidirectional"))
    )
    (net (code "53") (name "Net-(U3-C2+)") (class "Default")
      (node (ref "C21") (pin "2") (pinfunction "2_2") (pintype "passive"))
      (node (ref "U3") (pin "4") (pinfunction "C2+_4") (pintype "bidirectional"))
    )
    (net (code "54") (name "Net-(U3-C2-)") (class "Default")
      (node (ref "C21") (pin "1") (pinfunction "1_1") (pintype "passive"))
      (node (ref "U3") (pin "5") (pinfunction "C2-_5") (pintype "bidirectional"))
    )
    (net (code "55") (name "Net-(U3-V+)") (class "Default")
      (node (ref "C19") (pin "2") (pinfunction "2_2") (pintype "passive"))
      (node (ref "U3") (pin "2") (pinfunction "V+_2") (pintype "power_in"))
    )
    (net (code "56") (name "Net-(U3-V-)") (class "Default")
      (node (ref "C20") (pin "2") (pinfunction "2_2") (pintype "passive"))
      (node (ref "U3") (pin "6") (pinfunction "V-_6") (pintype "power_in"))
    )
    (net (code "57") (name "Net-(U4-2A)") (class "Default")
      (node (ref "R6") (pin "1") (pinfunction "1_1") (pintype "passive"))
      (node (ref "U4") (pin "12") (pinfunction "6Y_12") (pintype "output"))
      (node (ref "U4") (pin "3") (pinfunction "2A_3") (pintype "input"))
    )
    (net (code "58") (name "Net-(U4-3Y)") (class "Default")
      (node (ref "R12") (pin "1") (pinfunction "1_1") (pintype "passive"))
      (node (ref "U4") (pin "6") (pinfunction "3Y_6") (pintype "output"))
      (node (ref "U4") (pin "9") (pinfunction "4A_9") (pintype "input"))
    )
    (net (code "59") (name "Net-(U4-4Y)") (class "Default")
      (node (ref "D6") (pin "2") (pinfunction "2_2") (pintype "passive"))
      (node (ref "R10") (pin "2") (pinfunction "2_2") (pintype "passive"))
      (node (ref "U4") (pin "8") (pinfunction "4Y_8") (pintype "output"))
      (node (ref "U5") (pin "4") (pinfunction "DI_4") (pintype "input"))
    )
    (net (code "60") (name "Net-(U4-5A)") (class "Default")
      (node (ref "D6") (pin "1") (pinfunction "1_1") (pintype "passive"))
      (node (ref "R10") (pin "1") (pinfunction "1_1") (pintype "passive"))
      (node (ref "U4") (pin "11") (pinfunction "5A_11") (pintype "input"))
    )
    (net (code "61") (name "Net-(U4-5Y)") (class "Default")
      (node (ref "U4") (pin "10") (pinfunction "5Y_10") (pintype "output"))
      (node (ref "U5") (pin "2") (pinfunction "~{RE}_2") (pintype "input"))
      (node (ref "U5") (pin "3") (pinfunction "DE_3") (pintype "input"))
    )
    (net (code "62") (name "Net-(U4-6A)") (class "Default")
      (node (ref "U4") (pin "13") (pinfunction "6A_13") (pintype "input"))
      (node (ref "U5") (pin "1") (pinfunction "RO_1") (pintype "output"))
    )
    (net (code "63") (name "Net-(U6-C1+)") (class "Default")
      (node (ref "C27") (pin "2") (pinfunction "2_2") (pintype "passive"))
      (node (ref "U6") (pin "1") (pinfunction "C1+_1") (pintype "bidirectional"))
    )
    (net (code "64") (name "Net-(U6-C1-)") (class "Default")
      (node (ref "C27") (pin "1") (pinfunction "1_1") (pintype "passive"))
      (node (ref "U6") (pin "3") (pinfunction "C1-_3") (pintype "bidirectional"))
    )
    (net (code "65") (name "Net-(U6-C2+)") (class "Default")
      (node (ref "C30") (pin "2") (pinfunction "2_2") (pintype "passive"))
      (node (ref "U6") (pin "4") (pinfunction "C2+_4") (pintype "bidirectional"))
    )
    (net (code "66") (name "Net-(U6-C2-)") (class "Default")
      (node (ref "C30") (pin "1") (pinfunction "1_1") (pintype "passive"))
      (node (ref "U6") (pin "5") (pinfunction "C2-_5") (pintype "bidirectional"))
    )
    (net (code "67") (name "Net-(U6-V+)") (class "Default")
      (node (ref "C28") (pin "2") (pinfunction "2_2") (pintype "passive"))
      (node (ref "U6") (pin "2") (pinfunction "V+_2") (pintype "power_in"))
    )
    (net (code "68") (name "Net-(U6-V-)") (class "Default")
      (node (ref "C29") (pin "2") (pinfunction "2_2") (pintype "passive"))
      (node (ref "U6") (pin "6") (pinfunction "V-_6") (pintype "power_in"))
    )
    (net (code "69") (name "Net-(U7-C1+)") (class "Default")
      (node (ref "C33") (pin "2") (pinfunction "2_2") (pintype "passive"))
      (node (ref "U7") (pin "1") (pinfunction "C1+_1") (pintype "bidirectional"))
    )
    (net (code "70") (name "Net-(U7-C1-)") (class "Default")
      (node (ref "C33") (pin "1") (pinfunction "1_1") (pintype "passive"))
      (node (ref "U7") (pin "3") (pinfunction "C1-_3") (pintype "bidirectional"))
    )
    (net (code "71") (name "Net-(U7-C2+)") (class "Default")
      (node (ref "C36") (pin "2") (pinfunction "2_2") (pintype "passive"))
      (node (ref "U7") (pin "4") (pinfunction "C2+_4") (pintype "bidirectional"))
    )
    (net (code "72") (name "Net-(U7-C2-)") (class "Default")
      (node (ref "C36") (pin "1") (pinfunction "1_1") (pintype "passive"))
      (node (ref "U7") (pin "5") (pinfunction "C2-_5") (pintype "bidirectional"))
    )
    (net (code "73") (name "Net-(U7-V+)") (class "Default")
      (node (ref "C34") (pin "2") (pinfunction "2_2") (pintype "passive"))
      (node (ref "U7") (pin "2") (pinfunction "V+_2") (pintype "power_in"))
    )
    (net (code "74") (name "Net-(U7-V-)") (class "Default")
      (node (ref "C35") (pin "2") (pinfunction "2_2") (pintype "passive"))
      (node (ref "U7") (pin "6") (pinfunction "V-_6") (pintype "power_in"))
    )
    (net (code "75") (name "unconnected-(U4-1A-Pad1)") (class "Default")
      (node (ref "U4") (pin "1") (pinfunction "1A_1") (pintype "input+no_connect"))
    )
    (net (code "76") (name "unconnected-(U4-1Y-Pad2)") (class "Default")
      (node (ref "U4") (pin "2") (pinfunction "1Y_2") (pintype "output"))
    )
    (net (code "77") (name "unconnected-(U8-3-Pad4)") (class "Default")
      (node (ref "U8") (pin "4") (pinfunction "3_4") (pintype "bidirectional"))
    )
    (net (code "78") (name "unconnected-(U8-3-Pad11)") (class "Default")
      (node (ref "U8") (pin "11") (pinfunction "3_11") (pintype "bidirectional"))
    )
    (net (code "79") (name "unconnected-(U8-INH-Pad6)") (class "Default")
      (node (ref "U8") (pin "6") (pinfunction "INH_6") (pintype "input+no_connect"))
    )
  )
)
